# PWR.net
KiCad netlist of a schematic drawn in Altium Designer
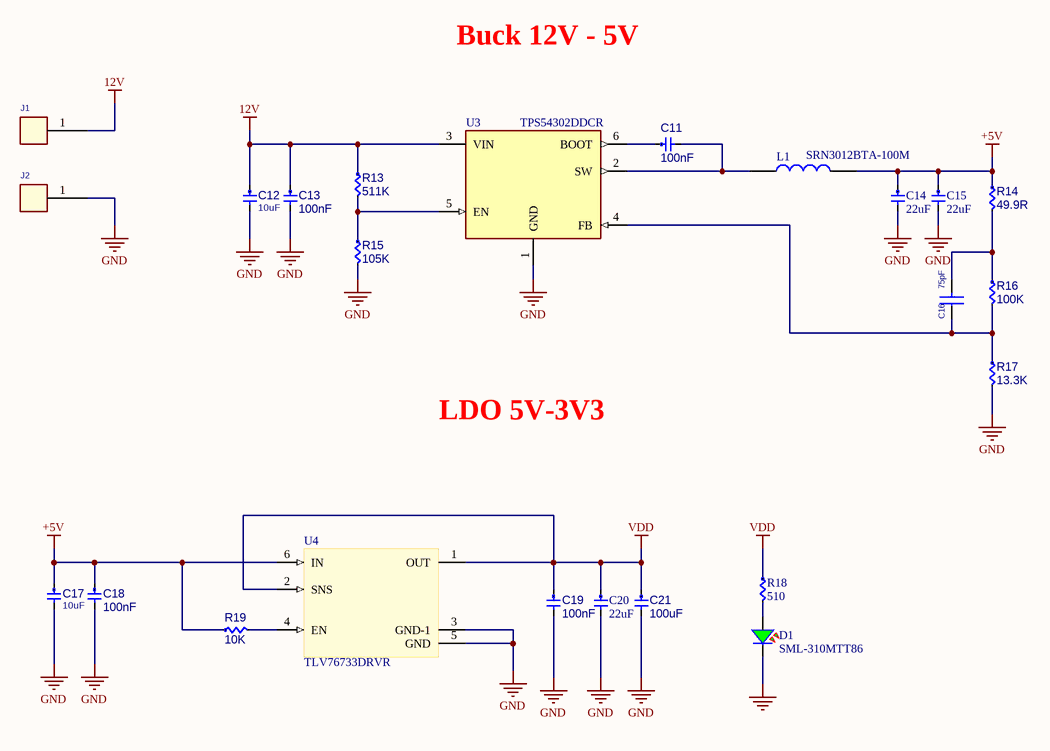
[diagram p0: PWR.SchDoc]

(export (version "E")
  (design (tool "Eeschema 10.0.6"))
  (components
    (comp (ref "C11")
      (value "CC0402KRX5R9BB104")
      (footprint "CAP0402")
      (description "CAP CER 0.1UF 50V X5R 0402")
      (fields
        (field (name "MANUFACTURER") "Yageo")
        (field (name "TOLERANCE") "10%")
        (field (name "CAPACITANCE") "100nF")
      )
      (libsource (lib "rtr") (part "CMP-00265-1"))
    )
    (comp (ref "C12")
      (value "GRM188R6YA106MA73D")
      (footprint "CAP0603")
      (description "CAP CER 10UF 35V X5R 0603")
      (fields
        (field (name "TOLERANCE") "20%")
        (field (name "VOLTAGE") "35V")
        (field (name "CAPACITANCE") "10uF")
      )
      (libsource (lib "rtr") (part "CMP-01031-1"))
    )
    (comp (ref "C13")
      (value "CC0402KRX5R9BB104")
      (footprint "CAP0402")
      (description "CAP CER 0.1UF 50V X5R 0402")
      (fields
        (field (name "MANUFACTURER") "Yageo")
        (field (name "TOLERANCE") "10%")
        (field (name "CAPACITANCE") "100nF")
      )
      (libsource (lib "rtr") (part "CMP-00265-1"))
    )
    (comp (ref "C14")
      (value "GRM158R61A226ME15D")
      (footprint "CAP0402")
      (description "CAP CER 22UF 10V X5R 0402")
      (fields
        (field (name "VOLTAGE") "10V")
        (field (name "TOLERANCE") "10%")
        (field (name "CAPACITANCE") "22uF")
      )
      (libsource (lib "CH961_CARRIER") (part "CMP-00520-1"))
    )
    (comp (ref "C15")
      (value "GRM158R61A226ME15D")
      (footprint "CAP0402")
      (description "CAP CER 22UF 10V X5R 0402")
      (fields
        (field (name "VOLTAGE") "10V")
        (field (name "TOLERANCE") "10%")
        (field (name "CAPACITANCE") "22uF")
      )
      (libsource (lib "CH961_CARRIER") (part "CMP-00520-1"))
    )
    (comp (ref "C16")
      (value "75pF")
      (footprint "CAP0402")
      (description "CAP CER 75PF 25V C0G/NP0 0402")
      (fields (field (name "MANUFACTURER") "YAGEO") (field (name "TOLERANCE") "5%"))
      (libsource (lib "motor MB1419") (part "CAP_Dup1_16"))
    )
    (comp (ref "C17")
      (value "GRM188R6YA106MA73D")
      (footprint "CAP0603")
      (description "CAP CER 10UF 35V X5R 0603")
      (fields
        (field (name "TOLERANCE") "20%")
        (field (name "VOLTAGE") "35V")
        (field (name "CAPACITANCE") "10uF")
      )
      (libsource (lib "rtr") (part "CMP-01031-1"))
    )
    (comp (ref "C18")
      (value "CC0402KRX5R9BB104")
      (footprint "CAP0402")
      (description "CAP CER 0.1UF 50V X5R 0402")
      (fields
        (field (name "MANUFACTURER") "Yageo")
        (field (name "TOLERANCE") "10%")
        (field (name "CAPACITANCE") "100nF")
      )
      (libsource (lib "rtr") (part "CMP-00265-1"))
    )
    (comp (ref "C19")
      (value "CC0402KRX5R9BB104")
      (footprint "CAP0402")
      (description "CAP CER 0.1UF 50V X5R 0402")
      (fields
        (field (name "MANUFACTURER") "Yageo")
        (field (name "TOLERANCE") "10%")
        (field (name "CAPACITANCE") "100nF")
      )
      (libsource (lib "rtr") (part "CMP-00265-1"))
    )
    (comp (ref "C20")
      (value "GRM158R61A226ME15D")
      (footprint "CAP0402")
      (description "CAP CER 22UF 10V X5R 0402")
      (fields
        (field (name "VOLTAGE") "10V")
        (field (name "TOLERANCE") "10%")
        (field (name "CAPACITANCE") "22uF")
      )
      (libsource (lib "CH961_CARRIER") (part "CMP-00520-1"))
    )
    (comp (ref "C21")
      (value "CL21A107MQYNNWE")
      (footprint "CAP0805")
      (description "CAP CER 100UF 6.3V X5R 0805")
      (fields (field (name "CAPACITANCE") "100uF") (field (name "TOLERANCE") "20%"))
      (libsource (lib "rtr") (part "CMP-00446-1"))
    )
    (comp (ref "D1")
      (value "SML-310MTT86")
      (footprint "LED0603 RED")
      (description "LED GREEN CLEAR 0603 SMD")
      (libsource (lib "HeraJetson_Modified") (part "CMP-01130-2"))
    )
    (comp (ref "J1")
      (value "CON1")
      (footprint "ESC PAD 3X4")
      (description "SOLDER PADS")
      (libsource (lib "motor MB1419") (part "CON1"))
    )
    (comp (ref "J2")
      (value "CON1")
      (footprint "ESC PAD 3X4")
      (description "SOLDER PADS")
      (libsource (lib "motor MB1419") (part "CON1"))
    )
    (comp (ref "L1")
      (value "SRN3012BTA-100M")
      (footprint "SRN3012BTA-100M")
      (description "10uH")
      (libsource (lib "SRN3012BTA-330M") (part "SRN3012BTA-330M"))
    )
    (comp (ref "R13")
      (value "511K")
      (footprint "RES0402")
      (description "RES SMD 511K OHM 1% 1/16W 0402")
      (fields (field (name "MANUFACTURER") "Yageo") (field (name "TOLERANCE") "1%"))
      (libsource (lib "rtr") (part "CMP-00299-1_1"))
    )
    (comp (ref "R14")
      (value "49.9R")
      (footprint "RES0402")
      (description "RES SMD 49.9R OHM 1% 1/16W 0402")
      (fields (field (name "MANUFACTURER") "Yageo") (field (name "TOLERANCE") "1%"))
      (libsource (lib "rtr") (part "CMP-00299-1_1"))
    )
    (comp (ref "R15")
      (value "105K")
      (footprint "RES0402")
      (description "RES SMD 105K OHM 1% 1/16W 0402")
      (fields (field (name "MANUFACTURER") "Yageo") (field (name "TOLERANCE") "1%"))
      (libsource (lib "rtr") (part "CMP-00299-1_1"))
    )
    (comp (ref "R16")
      (value "100K")
      (footprint "RES0402")
      (description "RES SMD 100K OHM 1% 1/16W 0402")
      (fields (field (name "MANUFACTURER") "Yageo") (field (name "TOLERANCE") "1%"))
      (libsource (lib "rtr") (part "CMP-00299-1_1"))
    )
    (comp (ref "R17")
      (value "13.3K")
      (footprint "RES0402")
      (description "RES SMD 13.3K OHM 1% 1/16W 0402")
      (fields (field (name "MANUFACTURER") "Yageo") (field (name "TOLERANCE") "1%"))
      (libsource (lib "rtr") (part "CMP-00299-1_1"))
    )
    (comp (ref "R18")
      (value "RT0402FRE07510RL")
      (footprint "RES0402")
      (description "RES SMD 510 OHM 1% 1/16W 0402")
      (fields
        (field (name "MANUFACTURER") "Yageo")
        (field (name "TOLERANCE") "1%")
        (field (name "RESISTANCE") "510")
      )
      (libsource (lib "CH961_CARRIER") (part "RC0402FR-0722KL"))
    )
    (comp (ref "R19")
      (value "CRCW040210K0JNED")
      (footprint "RES0402")
      (description "RES SMD 10K OHM 5% 1/16W 0402")
      (fields
        (field (name "RESISTANCE") "10K")
        (field (name "TOLERANCE") "5%")
        (field (name "MANUFACTURER") "Vishay Dale")
      )
      (libsource (lib "HeraJetson_Modified") (part "CMP-00034-1"))
    )
    (comp (ref "U3")
      (value "TPS54302DDCR")
      (footprint "SOT95P280X110-6N - duplicate")
      (description "4.5-V to 28-V Input, 3-A Output, EMI Friendly Synchronous Step-Down Converter")
      (fields (field (name "MF") "Texas Instruments"))
      (libsource (lib "RTR") (part "TPS54302DDCR"))
    )
    (comp (ref "U4")
      (value "TLV76733DRVR")
      (footprint "SON65P200X200X80-7N - duplicate")
      (description "Adjustable- and fixed-output, 1-A, 16-V, positive-voltage low-dropout (LDO) linear regulator")
      (fields (field (name "MF") "Texas Instruments"))
      (libsource (lib "TLV76733DRVR") (part "TLV76733DRVR"))
    )
  )
  (nets
    (net (code "1") (name "+5V") (class "Default")
      (node (ref "C14") (pin "1") (pinfunction "1_1") (pintype "passive"))
      (node (ref "C15") (pin "1") (pinfunction "1_1") (pintype "passive"))
      (node (ref "C17") (pin "1") (pinfunction "1_1") (pintype "passive"))
      (node (ref "C18") (pin "1") (pinfunction "1_1") (pintype "passive"))
      (node (ref "L1") (pin "2") (pinfunction "2_2") (pintype "passive"))
      (node (ref "R14") (pin "1") (pinfunction "1_1") (pintype "passive"))
      (node (ref "R19") (pin "1") (pinfunction "1_1") (pintype "passive"))
      (node (ref "U4") (pin "6") (pinfunction "IN_6") (pintype "input"))
    )
    (net (code "2") (name "12V") (class "Default")
      (node (ref "C12") (pin "1") (pinfunction "1_1") (pintype "passive"))
      (node (ref "C13") (pin "1") (pinfunction "1_1") (pintype "passive"))
      (node (ref "J1") (pin "1") (pinfunction "1_1") (pintype "passive"))
      (node (ref "R13") (pin "1") (pinfunction "1_1") (pintype "passive"))
      (node (ref "U3") (pin "3") (pinfunction "VIN_3") (pintype "power_in"))
    )
    (net (code "3") (name "GND") (class "Default")
      (node (ref "C12") (pin "2") (pinfunction "2_2") (pintype "passive"))
      (node (ref "C13") (pin "2") (pinfunction "2_2") (pintype "passive"))
      (node (ref "C14") (pin "2") (pinfunction "2_2") (pintype "passive"))
      (node (ref "C15") (pin "2") (pinfunction "2_2") (pintype "passive"))
      (node (ref "C17") (pin "2") (pinfunction "2_2") (pintype "passive"))
      (node (ref "C18") (pin "2") (pinfunction "2_2") (pintype "passive"))
      (node (ref "C19") (pin "2") (pinfunction "2_2") (pintype "passive"))
      (node (ref "C20") (pin "2") (pinfunction "2_2") (pintype "passive"))
      (node (ref "C21") (pin "2") (pinfunction "2_2") (pintype "passive"))
      (node (ref "D1") (pin "1") (pinfunction "1_1") (pintype "passive"))
      (node (ref "J2") (pin "1") (pinfunction "1_1") (pintype "passive"))
      (node (ref "R15") (pin "2") (pinfunction "2_2") (pintype "passive"))
      (node (ref "R17") (pin "2") (pinfunction "2_2") (pintype "passive"))
      (node (ref "U3") (pin "1") (pinfunction "GND_1") (pintype "power_in"))
      (node (ref "U4") (pin "3") (pinfunction "GND-1_3") (pintype "power_in"))
      (node (ref "U4") (pin "5") (pinfunction "GND_5") (pintype "power_in"))
    )
    (net (code "4") (name "Net-(C16-Pad2)") (class "Default")
      (node (ref "C16") (pin "2") (pinfunction "2_2") (pintype "passive"))
      (node (ref "R14") (pin "2") (pinfunction "2_2") (pintype "passive"))
      (node (ref "R16") (pin "1") (pinfunction "1_1") (pintype "passive"))
    )
    (net (code "5") (name "Net-(D1-Pad2)") (class "Default")
      (node (ref "D1") (pin "2") (pinfunction "2_2") (pintype "passive"))
      (node (ref "R18") (pin "2") (pinfunction "2_2") (pintype "passive"))
    )
    (net (code "6") (name "Net-(U3-BOOT)") (class "Default")
      (node (ref "C11") (pin "1") (pinfunction "1_1") (pintype "passive"))
      (node (ref "U3") (pin "6") (pinfunction "BOOT_6") (pintype "output"))
    )
    (net (code "7") (name "Net-(U3-EN)") (class "Default")
      (node (ref "R13") (pin "2") (pinfunction "2_2") (pintype "passive"))
      (node (ref "R15") (pin "1") (pinfunction "1_1") (pintype "passive"))
      (node (ref "U3") (pin "5") (pinfunction "EN_5") (pintype "input"))
    )
    (net (code "8") (name "Net-(U3-FB)") (class "Default")
      (node (ref "C16") (pin "1") (pinfunction "1_1") (pintype "passive"))
      (node (ref "R16") (pin "2") (pinfunction "2_2") (pintype "passive"))
      (node (ref "R17") (pin "1") (pinfunction "1_1") (pintype "passive"))
      (node (ref "U3") (pin "4") (pinfunction "FB_4") (pintype "input"))
    )
    (net (code "9") (name "Net-(U3-SW)") (class "Default")
      (node (ref "C11") (pin "2") (pinfunction "2_2") (pintype "passive"))
      (node (ref "L1") (pin "1") (pinfunction "1_1") (pintype "passive"))
      (node (ref "U3") (pin "2") (pinfunction "SW_2") (pintype "output"))
    )
    (net (code "10") (name "Net-(U4-EN)") (class "Default")
      (node (ref "R19") (pin "2") (pinfunction "2_2") (pintype "passive"))
      (node (ref "U4") (pin "4") (pinfunction "EN_4") (pintype "input"))
    )
    (net (code "11") (name "VDD") (class "Default")
      (node (ref "C19") (pin "1") (pinfunction "1_1") (pintype "passive"))
      (node (ref "C20") (pin "1") (pinfunction "1_1") (pintype "passive"))
      (node (ref "C21") (pin "1") (pinfunction "1_1") (pintype "passive"))
      (node (ref "R18") (pin "1") (pinfunction "1_1") (pintype "passive"))
      (node (ref "U4") (pin "1") (pinfunction "OUT_1") (pintype "power_in"))
      (node (ref "U4") (pin "2") (pinfunction "SNS_2") (pintype "input"))
    )
  )
)
